# RF.net
KiCad netlist of a schematic drawn in Altium Designer
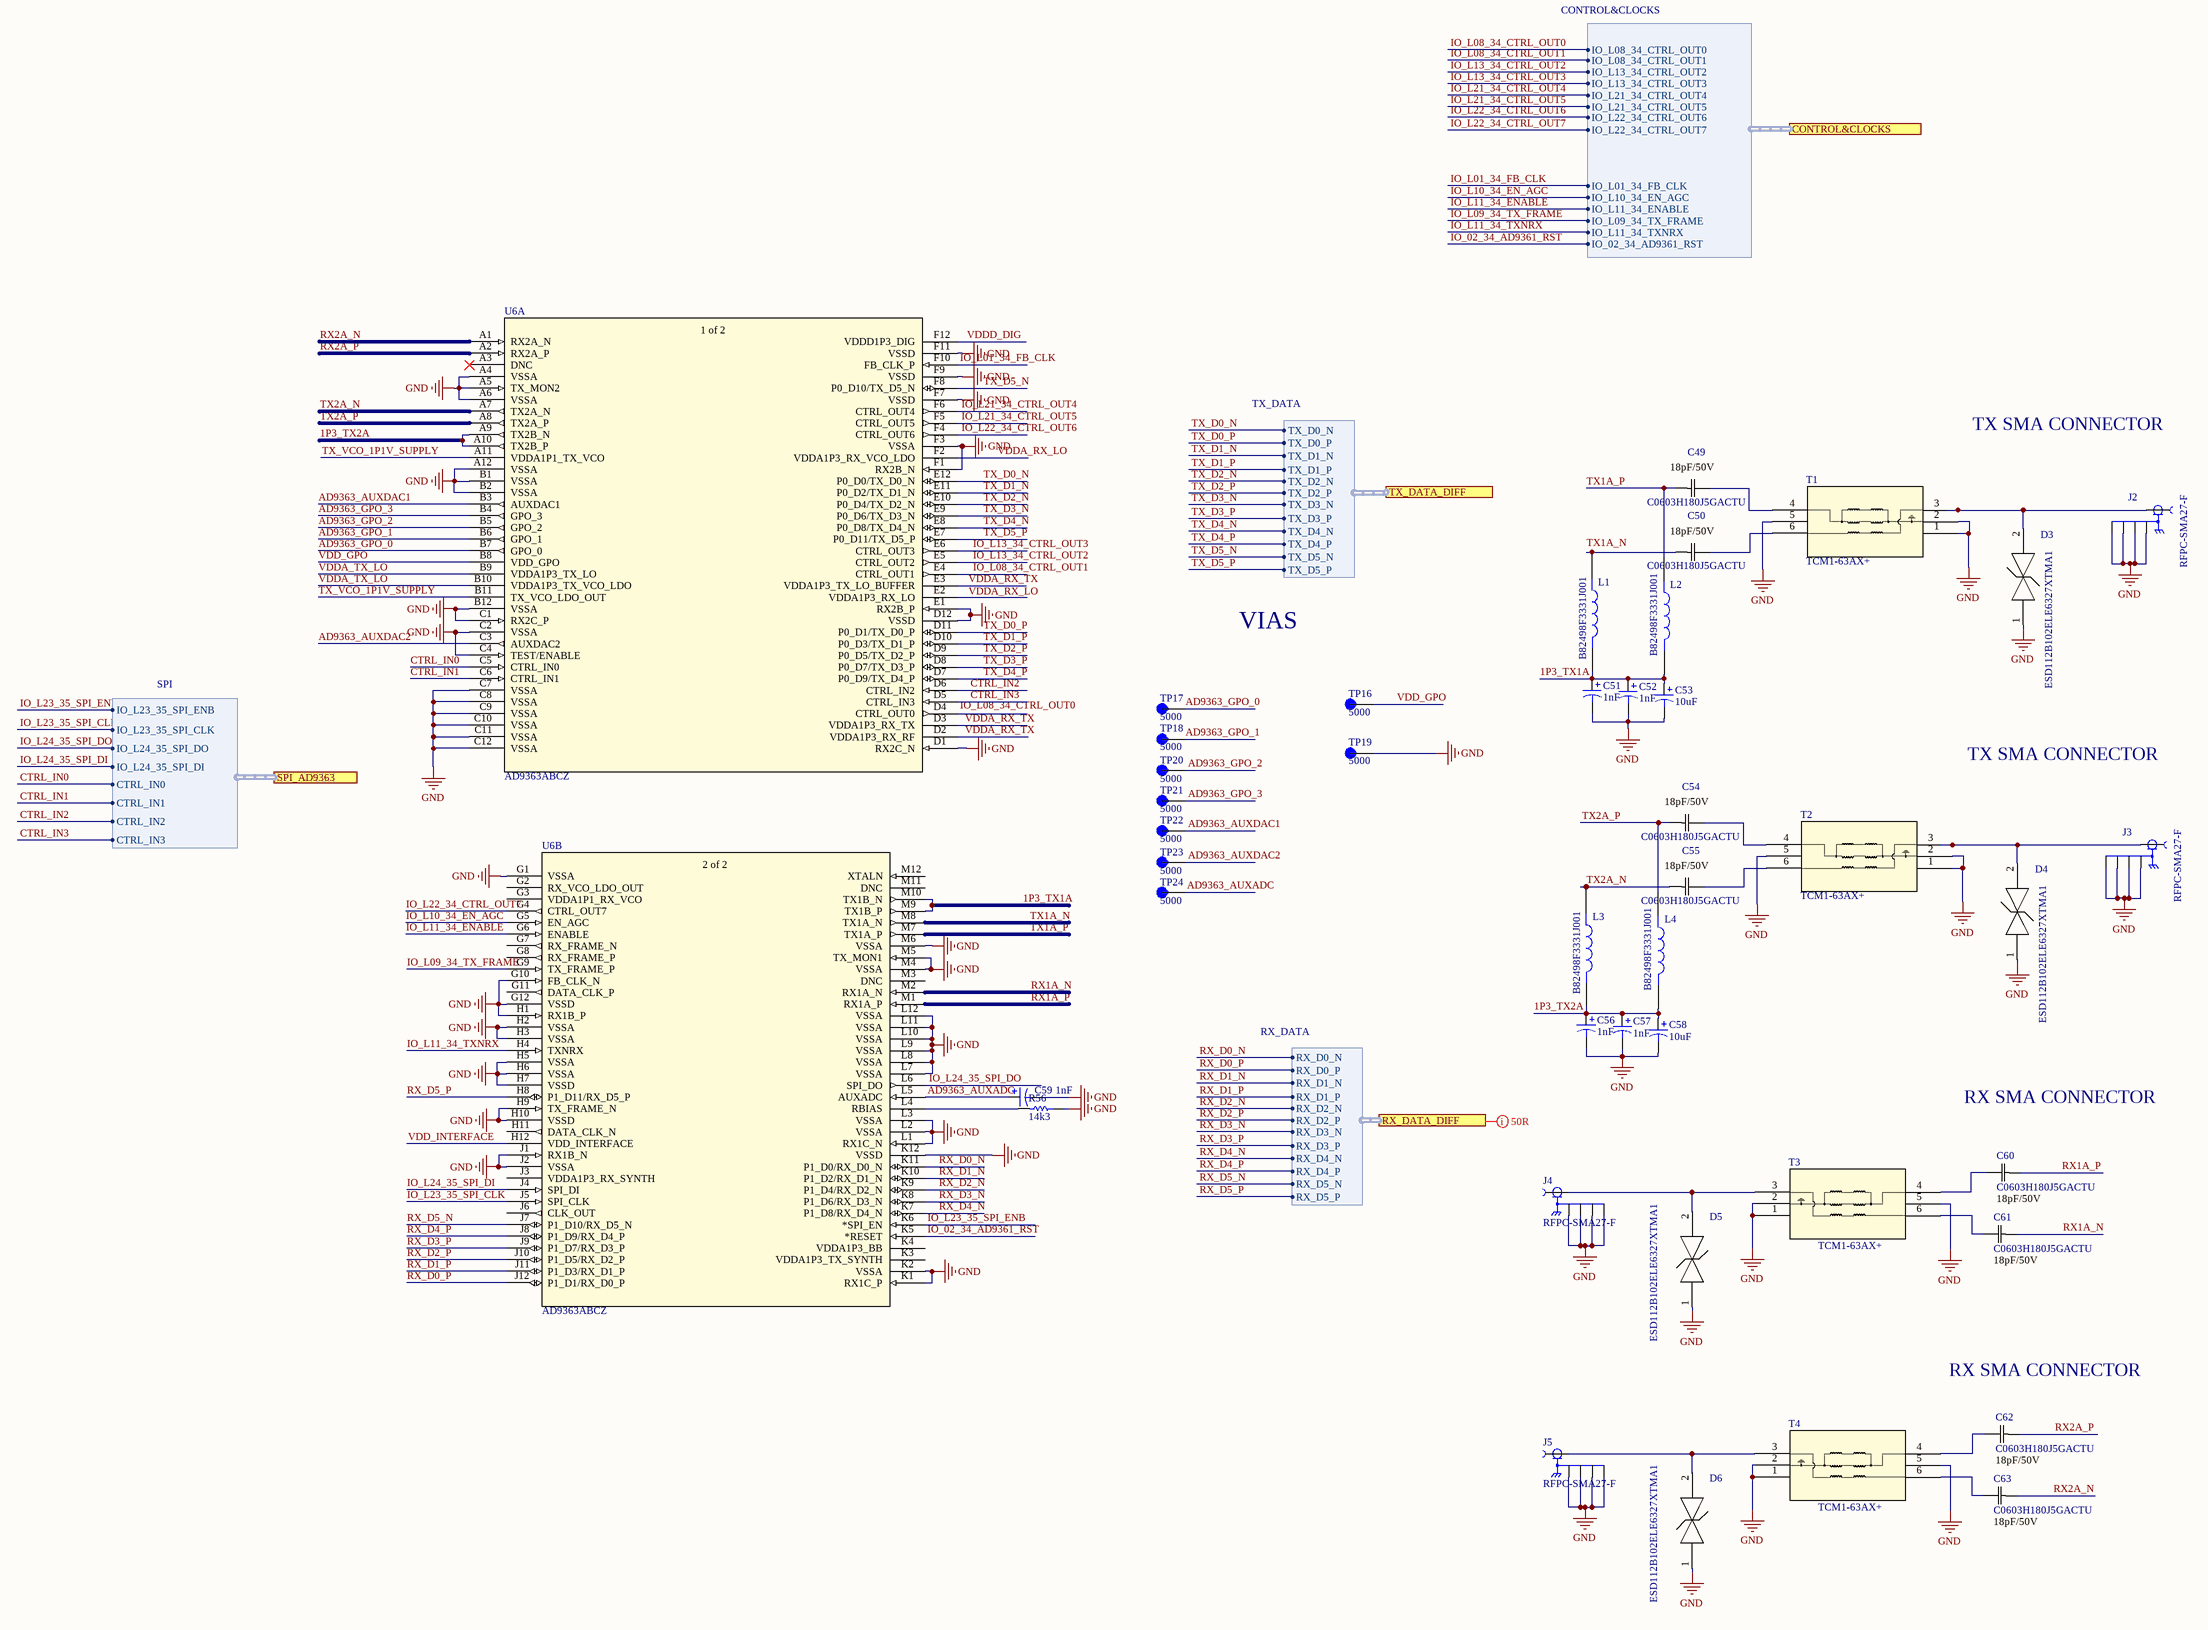
[diagram p0: RF.SchDoc]

(export (version "E")
  (design (tool "Eeschema 10.0.6"))
  (components
    (comp (ref "C49")
      (value "C0603H180J5GACTU")
      (footprint "CAPC17595_87N_KEM")
      (description "No Description Available")
      (fields (field (name "REFDES") "18pF/50V"))
      (libsource (lib "C0603H180J5GACTU") (part "C0603H180J5GACTU"))
    )
    (comp (ref "C50")
      (value "C0603H180J5GACTU")
      (footprint "CAPC17595_87N_KEM")
      (description "No Description Available")
      (fields (field (name "REFDES") "18pF/50V"))
      (libsource (lib "C0603H180J5GACTU") (part "C0603H180J5GACTU"))
    )
    (comp (ref "C51")
      (value "1nF")
      (footprint "C0805")
      (description "Polarized Capacitor (Surface Mount)")
      (fields (field (name "Comment") "Cap Pol3") (field (name "PUBLISHER") "Altium Limited"))
      (libsource (lib "Miscellaneous Devices") (part "Cap Pol3"))
    )
    (comp (ref "C52")
      (value "1nF")
      (footprint "C0805")
      (description "Polarized Capacitor (Surface Mount)")
      (fields (field (name "Comment") "Cap Pol3") (field (name "PUBLISHER") "Altium Limited"))
      (libsource (lib "Miscellaneous Devices") (part "Cap Pol3"))
    )
    (comp (ref "C53")
      (value "10uF")
      (footprint "C0805")
      (description "Polarized Capacitor (Surface Mount)")
      (fields (field (name "Comment") "Cap Pol3") (field (name "PUBLISHER") "Altium Limited"))
      (libsource (lib "Miscellaneous Devices") (part "Cap Pol3"))
    )
    (comp (ref "C54")
      (value "C0603H180J5GACTU")
      (footprint "CAPC17595_87N_KEM")
      (description "No Description Available")
      (fields (field (name "REFDES") "18pF/50V"))
      (libsource (lib "C0603H180J5GACTU") (part "C0603H180J5GACTU"))
    )
    (comp (ref "C55")
      (value "C0603H180J5GACTU")
      (footprint "CAPC17595_87N_KEM")
      (description "No Description Available")
      (fields (field (name "REFDES") "18pF/50V"))
      (libsource (lib "C0603H180J5GACTU") (part "C0603H180J5GACTU"))
    )
    (comp (ref "C56")
      (value "1nF")
      (footprint "C0805")
      (description "Polarized Capacitor (Surface Mount)")
      (fields (field (name "Comment") "Cap Pol3") (field (name "PUBLISHER") "Altium Limited"))
      (libsource (lib "Miscellaneous Devices") (part "Cap Pol3"))
    )
    (comp (ref "C57")
      (value "1nF")
      (footprint "C0805")
      (description "Polarized Capacitor (Surface Mount)")
      (fields (field (name "Comment") "Cap Pol3") (field (name "PUBLISHER") "Altium Limited"))
      (libsource (lib "Miscellaneous Devices") (part "Cap Pol3"))
    )
    (comp (ref "C58")
      (value "10uF")
      (footprint "C0805")
      (description "Polarized Capacitor (Surface Mount)")
      (fields (field (name "Comment") "Cap Pol3") (field (name "PUBLISHER") "Altium Limited"))
      (libsource (lib "Miscellaneous Devices") (part "Cap Pol3"))
    )
    (comp (ref "C59")
      (value "1nF")
      (footprint "C0805")
      (description "Polarized Capacitor (Surface Mount)")
      (fields (field (name "Comment") "Cap Pol3") (field (name "PUBLISHER") "Altium Limited"))
      (libsource (lib "Miscellaneous Devices") (part "Cap Pol3"))
    )
    (comp (ref "C60")
      (value "C0603H180J5GACTU")
      (footprint "CAPC17595_87N_KEM")
      (description "No Description Available")
      (fields (field (name "REFDES") "18pF/50V"))
      (libsource (lib "C0603H180J5GACTU") (part "C0603H180J5GACTU"))
    )
    (comp (ref "C61")
      (value "C0603H180J5GACTU")
      (footprint "CAPC17595_87N_KEM")
      (description "No Description Available")
      (fields (field (name "REFDES") "18pF/50V"))
      (libsource (lib "C0603H180J5GACTU") (part "C0603H180J5GACTU"))
    )
    (comp (ref "C62")
      (value "C0603H180J5GACTU")
      (footprint "CAPC17595_87N_KEM")
      (description "No Description Available")
      (fields (field (name "REFDES") "18pF/50V"))
      (libsource (lib "C0603H180J5GACTU") (part "C0603H180J5GACTU"))
    )
    (comp (ref "C63")
      (value "C0603H180J5GACTU")
      (footprint "CAPC17595_87N_KEM")
      (description "No Description Available")
      (fields (field (name "REFDES") "18pF/50V"))
      (libsource (lib "C0603H180J5GACTU") (part "C0603H180J5GACTU"))
    )
    (comp (ref "D3")
      (value "ESD112B102ELE6327XTMA1")
      (footprint "DIODFN100X60X43-2N")
      (description "TVS RF PLUTO")
      (libsource (lib "TVSESD112B102ELE6327XTMA1") (part "ESD112B102ELE6327XTMA1"))
    )
    (comp (ref "D4")
      (value "ESD112B102ELE6327XTMA1")
      (footprint "DIODFN100X60X43-2N")
      (description "TVS RF PLUTO")
      (libsource (lib "TVSESD112B102ELE6327XTMA1") (part "ESD112B102ELE6327XTMA1"))
    )
    (comp (ref "D5")
      (value "ESD112B102ELE6327XTMA1")
      (footprint "DIODFN100X60X43-2N")
      (description "TVS RF PLUTO")
      (libsource (lib "TVSESD112B102ELE6327XTMA1") (part "ESD112B102ELE6327XTMA1"))
    )
    (comp (ref "D6")
      (value "ESD112B102ELE6327XTMA1")
      (footprint "DIODFN100X60X43-2N")
      (description "TVS RF PLUTO")
      (libsource (lib "TVSESD112B102ELE6327XTMA1") (part "ESD112B102ELE6327XTMA1"))
    )
    (comp (ref "J2")
      (value "RFPC-SMA27-F")
      (footprint "GRADCONN_RFPC-SMA27-F")
      (fields (field (name "MF") "{'manufacturer': u'GCT (Gradconn)'}"))
      (libsource (lib "RFPC-SMA27-F") (part "RFPC-SMA27-F"))
    )
    (comp (ref "J3")
      (value "RFPC-SMA27-F")
      (footprint "GRADCONN_RFPC-SMA27-F")
      (fields (field (name "MF") "{'manufacturer': u'GCT (Gradconn)'}"))
      (libsource (lib "RFPC-SMA27-F") (part "RFPC-SMA27-F"))
    )
    (comp (ref "J4")
      (value "RFPC-SMA27-F")
      (footprint "GRADCONN_RFPC-SMA27-F")
      (fields (field (name "MF") "{'manufacturer': u'GCT (Gradconn)'}"))
      (libsource (lib "") (part "RFPC-SMA27-F_1"))
    )
    (comp (ref "J5")
      (value "RFPC-SMA27-F")
      (footprint "GRADCONN_RFPC-SMA27-F")
      (fields (field (name "MF") "{'manufacturer': u'GCT (Gradconn)'}"))
      (libsource (lib "") (part "RFPC-SMA27-F_1"))
    )
    (comp (ref "L1")
      (value "B82498F3331J001")
      (footprint "IND_B82498F3331J001")
      (fields (field (name "MF") "TDK"))
      (libsource (lib "ID_330nH_B82498F3331J001") (part "B82498F3331J001"))
    )
    (comp (ref "L2")
      (value "B82498F3331J001")
      (footprint "IND_B82498F3331J001")
      (fields (field (name "MF") "TDK"))
      (libsource (lib "ID_330nH_B82498F3331J001") (part "B82498F3331J001"))
    )
    (comp (ref "L3")
      (value "B82498F3331J001")
      (footprint "IND_B82498F3331J001")
      (fields (field (name "MF") "TDK"))
      (libsource (lib "ID_330nH_B82498F3331J001") (part "B82498F3331J001"))
    )
    (comp (ref "L4")
      (value "B82498F3331J001")
      (footprint "IND_B82498F3331J001")
      (fields (field (name "MF") "TDK"))
      (libsource (lib "ID_330nH_B82498F3331J001") (part "B82498F3331J001"))
    )
    (comp (ref "R56")
      (value "14k3")
      (footprint "0603")
      (description "Resistor")
      (fields
        (field (name "MANUFACTURER") "Generic Components")
        (field (name "Comment") "Res1")
        (field (name "PUBLISHER") "Altium Limited")
      )
      (libsource (lib "lib_protel_HC") (part "Res1_1"))
    )
    (comp (ref "T1")
      (value "TCM1-63AX+")
      (footprint "DB1627_MNC")
      (description "No Description Available")
      (libsource (lib "TCM1-63AX&plus_") (part "TCM1-63AX+"))
    )
    (comp (ref "T2")
      (value "TCM1-63AX+")
      (footprint "DB1627_MNC")
      (description "No Description Available")
      (libsource (lib "TCM1-63AX&plus_") (part "TCM1-63AX+"))
    )
    (comp (ref "T3")
      (value "TCM1-63AX+")
      (footprint "DB1627_MNC")
      (description "No Description Available")
      (libsource (lib "TCM1-63AX&plus_") (part "TCM1-63AX+"))
    )
    (comp (ref "T4")
      (value "TCM1-63AX+")
      (footprint "DB1627_MNC")
      (description "No Description Available")
      (libsource (lib "TCM1-63AX&plus_") (part "TCM1-63AX+"))
    )
    (comp (ref "TP16")
      (value "5000")
      (footprint "KEYSTONE_5000")
      (fields (field (name "MF") "Keystone Electronics"))
      (libsource (lib "5000") (part "5000"))
    )
    (comp (ref "TP17")
      (value "5000")
      (footprint "KEYSTONE_5000")
      (fields (field (name "MF") "Keystone Electronics"))
      (libsource (lib "5000") (part "5000"))
    )
    (comp (ref "TP18")
      (value "5000")
      (footprint "KEYSTONE_5000")
      (fields (field (name "MF") "Keystone Electronics"))
      (libsource (lib "5000") (part "5000"))
    )
    (comp (ref "TP19")
      (value "5000")
      (footprint "KEYSTONE_5000")
      (fields (field (name "MF") "Keystone Electronics"))
      (libsource (lib "5000") (part "5000"))
    )
    (comp (ref "TP20")
      (value "5000")
      (footprint "KEYSTONE_5000")
      (fields (field (name "MF") "Keystone Electronics"))
      (libsource (lib "5000") (part "5000"))
    )
    (comp (ref "TP21")
      (value "5000")
      (footprint "KEYSTONE_5000")
      (fields (field (name "MF") "Keystone Electronics"))
      (libsource (lib "5000") (part "5000"))
    )
    (comp (ref "TP22")
      (value "5000")
      (footprint "KEYSTONE_5000")
      (fields (field (name "MF") "Keystone Electronics"))
      (libsource (lib "5000") (part "5000"))
    )
    (comp (ref "TP23")
      (value "5000")
      (footprint "KEYSTONE_5000")
      (fields (field (name "MF") "Keystone Electronics"))
      (libsource (lib "5000") (part "5000"))
    )
    (comp (ref "TP24")
      (value "5000")
      (footprint "KEYSTONE_5000")
      (fields (field (name "MF") "Keystone Electronics"))
      (libsource (lib "5000") (part "5000"))
    )
    (comp (ref "U6")
      (value "AD9363ABCZ")
      (footprint "BC-144-7_ADI")
      (description "No Description Available")
      (libsource (lib "AD9363ABCZ") (part "AD9363ABCZ"))
    )
  )
  (nets
    (net (code "5") (name "/1P3_TX1A") (class "Default")
      (node (ref "C51") (pin "1") (pinfunction "1_1") (pintype "passive"))
      (node (ref "C52") (pin "1") (pinfunction "1_1") (pintype "passive"))
      (node (ref "C53") (pin "1") (pinfunction "1_1") (pintype "passive"))
      (node (ref "L1") (pin "1") (pinfunction "1_1") (pintype "passive"))
      (node (ref "L2") (pin "1") (pinfunction "1_1") (pintype "passive"))
      (node (ref "U6") (pin "M10") (pinfunction "TX1B_N_M10") (pintype "output"))
      (node (ref "U6") (pin "M9") (pinfunction "TX1B_P_M9") (pintype "output"))
    )
    (net (code "6") (name "/1P3_TX2A") (class "Default")
      (node (ref "C56") (pin "1") (pinfunction "1_1") (pintype "passive"))
      (node (ref "C57") (pin "1") (pinfunction "1_1") (pintype "passive"))
      (node (ref "C58") (pin "1") (pinfunction "1_1") (pintype "passive"))
      (node (ref "L3") (pin "1") (pinfunction "1_1") (pintype "passive"))
      (node (ref "L4") (pin "1") (pinfunction "1_1") (pintype "passive"))
      (node (ref "U6") (pin "A10") (pinfunction "TX2B_P_A10") (pintype "output"))
      (node (ref "U6") (pin "A9") (pinfunction "TX2B_N_A9") (pintype "output"))
    )
    (net (code "7") (name "/AD9363_AUXADC") (class "Default")
      (node (ref "C59") (pin "1") (pinfunction "1_1") (pintype "passive"))
      (node (ref "TP24") (pin "TP") (pinfunction "TP_TP") (pintype "passive"))
      (node (ref "U6") (pin "L5") (pinfunction "AUXADC_L5") (pintype "input"))
    )
    (net (code "8") (name "/AD9363_AUXDAC1") (class "Default")
      (node (ref "TP22") (pin "TP") (pinfunction "TP_TP") (pintype "passive"))
      (node (ref "U6") (pin "B3") (pinfunction "AUXDAC1_B3") (pintype "output"))
    )
    (net (code "9") (name "/AD9363_AUXDAC2") (class "Default")
      (node (ref "TP23") (pin "TP") (pinfunction "TP_TP") (pintype "passive"))
      (node (ref "U6") (pin "C3") (pinfunction "AUXDAC2_C3") (pintype "output"))
    )
    (net (code "10") (name "/AD9363_GPO_0") (class "Default")
      (node (ref "TP17") (pin "TP") (pinfunction "TP_TP") (pintype "passive"))
      (node (ref "U6") (pin "B7") (pinfunction "GPO_0_B7") (pintype "output"))
    )
    (net (code "11") (name "/AD9363_GPO_1") (class "Default")
      (node (ref "TP18") (pin "TP") (pinfunction "TP_TP") (pintype "passive"))
      (node (ref "U6") (pin "B6") (pinfunction "GPO_1_B6") (pintype "output"))
    )
    (net (code "12") (name "/AD9363_GPO_2") (class "Default")
      (node (ref "TP20") (pin "TP") (pinfunction "TP_TP") (pintype "passive"))
      (node (ref "U6") (pin "B5") (pinfunction "GPO_2_B5") (pintype "output"))
    )
    (net (code "13") (name "/AD9363_GPO_3") (class "Default")
      (node (ref "TP21") (pin "TP") (pinfunction "TP_TP") (pintype "passive"))
      (node (ref "U6") (pin "B4") (pinfunction "GPO_3_B4") (pintype "output"))
    )
    (net (code "14") (name "/CTRL_IN0") (class "Default")
      (node (ref "U6") (pin "C5") (pinfunction "CTRL_IN0_C5") (pintype "input"))
    )
    (net (code "15") (name "/CTRL_IN1") (class "Default")
      (node (ref "U6") (pin "C6") (pinfunction "CTRL_IN1_C6") (pintype "input"))
    )
    (net (code "16") (name "/CTRL_IN2") (class "Default")
      (node (ref "U6") (pin "D6") (pinfunction "CTRL_IN2_D6") (pintype "input"))
    )
    (net (code "17") (name "/CTRL_IN3") (class "Default")
      (node (ref "U6") (pin "D5") (pinfunction "CTRL_IN3_D5") (pintype "input"))
    )
    (net (code "18") (name "/IO_02_34_AD9361_RST") (class "Default")
      (node (ref "U6") (pin "K5") (pinfunction "*RESET_K5") (pintype "input"))
    )
    (net (code "19") (name "/IO_L01_34_FB_CLK") (class "Default")
      (node (ref "U6") (pin "F10") (pinfunction "FB_CLK_P_F10") (pintype "input"))
    )
    (net (code "21") (name "/IO_L08_34_CTRL_OUT1") (class "Default")
      (node (ref "U6") (pin "E4") (pinfunction "CTRL_OUT1_E4") (pintype "output"))
    )
    (net (code "22") (name "/IO_L09_34_TX_FRAME") (class "Default")
      (node (ref "U6") (pin "G9") (pinfunction "TX_FRAME_P_G9") (pintype "input"))
    )
    (net (code "23") (name "/IO_L10_34_EN_AGC") (class "Default")
      (node (ref "U6") (pin "G5") (pinfunction "EN_AGC_G5") (pintype "input"))
    )
    (net (code "24") (name "/IO_L11_34_ENABLE") (class "Default")
      (node (ref "U6") (pin "G6") (pinfunction "ENABLE_G6") (pintype "input"))
    )
    (net (code "25") (name "/IO_L11_34_TXNRX") (class "Default")
      (node (ref "U6") (pin "H4") (pinfunction "TXNRX_H4") (pintype "input"))
    )
    (net (code "26") (name "/IO_L13_34_CTRL_OUT2") (class "Default")
      (node (ref "U6") (pin "E5") (pinfunction "CTRL_OUT2_E5") (pintype "output"))
    )
    (net (code "27") (name "/IO_L13_34_CTRL_OUT3") (class "Default")
      (node (ref "U6") (pin "E6") (pinfunction "CTRL_OUT3_E6") (pintype "output"))
    )
    (net (code "28") (name "/IO_L21_34_CTRL_OUT4") (class "Default")
      (node (ref "U6") (pin "F6") (pinfunction "CTRL_OUT4_F6") (pintype "output"))
    )
    (net (code "29") (name "/IO_L21_34_CTRL_OUT5") (class "Default")
      (node (ref "U6") (pin "F5") (pinfunction "CTRL_OUT5_F5") (pintype "output"))
    )
    (net (code "30") (name "/IO_L22_34_CTRL_OUT6") (class "Default")
      (node (ref "U6") (pin "F4") (pinfunction "CTRL_OUT6_F4") (pintype "output"))
    )
    (net (code "31") (name "/IO_L22_34_CTRL_OUT7") (class "Default")
      (node (ref "U6") (pin "G4") (pinfunction "CTRL_OUT7_G4") (pintype "output"))
    )
    (net (code "32") (name "/IO_L23_35_SPI_CLK") (class "Default")
      (node (ref "U6") (pin "J5") (pinfunction "SPI_CLK_J5") (pintype "input"))
    )
    (net (code "33") (name "/IO_L23_35_SPI_ENB") (class "Default")
      (node (ref "U6") (pin "K6") (pinfunction "*SPI_EN_K6") (pintype "input"))
    )
    (net (code "34") (name "/IO_L24_35_SPI_DI") (class "Default")
      (node (ref "U6") (pin "J4") (pinfunction "SPI_DI_J4") (pintype "input"))
    )
    (net (code "35") (name "/IO_L24_35_SPI_DO") (class "Default")
      (node (ref "U6") (pin "L6") (pinfunction "SPI_DO_L6") (pintype "output"))
    )
    (net (code "36") (name "/RX1A_N") (class "Default")
      (node (ref "C61") (pin "1") (pinfunction "1_1") (pintype "passive"))
      (node (ref "U6") (pin "M2") (pinfunction "RX1A_N_M2") (pintype "input"))
    )
    (net (code "37") (name "/RX1A_P") (class "Default")
      (node (ref "C60") (pin "1") (pinfunction "1_1") (pintype "passive"))
      (node (ref "U6") (pin "M1") (pinfunction "RX1A_P_M1") (pintype "input"))
    )
    (net (code "38") (name "/RX2A_N") (class "Default")
      (node (ref "C63") (pin "1") (pinfunction "1_1") (pintype "passive"))
      (node (ref "U6") (pin "A1") (pinfunction "RX2A_N_A1") (pintype "input"))
    )
    (net (code "39") (name "/RX2A_P") (class "Default")
      (node (ref "C62") (pin "1") (pinfunction "1_1") (pintype "passive"))
      (node (ref "U6") (pin "A2") (pinfunction "RX2A_P_A2") (pintype "input"))
    )
    (net (code "40") (name "/RX_D0_N") (class "Default")
      (node (ref "U6") (pin "K11") (pinfunction "P1_D0/RX_D0_N_K11") (pintype "bidirectional"))
    )
    (net (code "41") (name "/RX_D0_P") (class "Default")
      (node (ref "U6") (pin "J12") (pinfunction "P1_D1/RX_D0_P_J12") (pintype "bidirectional"))
    )
    (net (code "42") (name "/RX_D1_N") (class "Default")
      (node (ref "U6") (pin "K10") (pinfunction "P1_D2/RX_D1_N_K10") (pintype "bidirectional"))
    )
    (net (code "43") (name "/RX_D1_P") (class "Default")
      (node (ref "U6") (pin "J11") (pinfunction "P1_D3/RX_D1_P_J11") (pintype "bidirectional"))
    )
    (net (code "44") (name "/RX_D2_N") (class "Default")
      (node (ref "U6") (pin "K9") (pinfunction "P1_D4/RX_D2_N_K9") (pintype "bidirectional"))
    )
    (net (code "45") (name "/RX_D2_P") (class "Default")
      (node (ref "U6") (pin "J10") (pinfunction "P1_D5/RX_D2_P_J10") (pintype "bidirectional"))
    )
    (net (code "46") (name "/RX_D3_N") (class "Default")
      (node (ref "U6") (pin "K8") (pinfunction "P1_D6/RX_D3_N_K8") (pintype "bidirectional"))
    )
    (net (code "47") (name "/RX_D3_P") (class "Default")
      (node (ref "U6") (pin "J9") (pinfunction "P1_D7/RX_D3_P_J9") (pintype "bidirectional"))
    )
    (net (code "48") (name "/RX_D4_N") (class "Default")
      (node (ref "U6") (pin "K7") (pinfunction "P1_D8/RX_D4_N_K7") (pintype "bidirectional"))
    )
    (net (code "49") (name "/RX_D4_P") (class "Default")
      (node (ref "U6") (pin "J8") (pinfunction "P1_D9/RX_D4_P_J8") (pintype "bidirectional"))
    )
    (net (code "50") (name "/RX_D5_N") (class "Default")
      (node (ref "U6") (pin "J7") (pinfunction "P1_D10/RX_D5_N_J7") (pintype "bidirectional"))
    )
    (net (code "51") (name "/RX_D5_P") (class "Default")
      (node (ref "U6") (pin "H8") (pinfunction "P1_D11/RX_D5_P_H8") (pintype "bidirectional"))
    )
    (net (code "52") (name "/TX1A_N") (class "Default")
      (node (ref "U6") (pin "M8") (pinfunction "TX1A_N_M8") (pintype "output"))
    )
    (net (code "53") (name "/TX1A_P") (class "Default")
      (node (ref "C49") (pin "1") (pinfunction "1_1") (pintype "passive"))
      (node (ref "L2") (pin "2") (pinfunction "2_2") (pintype "passive"))
      (node (ref "U6") (pin "M7") (pinfunction "TX1A_P_M7") (pintype "output"))
    )
    (net (code "54") (name "/TX2A_N") (class "Default")
      (node (ref "C55") (pin "1") (pinfunction "1_1") (pintype "passive"))
      (node (ref "L3") (pin "2") (pinfunction "2_2") (pintype "passive"))
      (node (ref "U6") (pin "A7") (pinfunction "TX2A_N_A7") (pintype "output"))
    )
    (net (code "55") (name "/TX2A_P") (class "Default")
      (node (ref "C54") (pin "1") (pinfunction "1_1") (pintype "passive"))
      (node (ref "L4") (pin "2") (pinfunction "2_2") (pintype "passive"))
      (node (ref "U6") (pin "A8") (pinfunction "TX2A_P_A8") (pintype "output"))
    )
    (net (code "56") (name "/TX_D0_N") (class "Default")
      (node (ref "U6") (pin "E12") (pinfunction "P0_D0/TX_D0_N_E12") (pintype "bidirectional"))
    )
    (net (code "57") (name "/TX_D0_P") (class "Default")
      (node (ref "U6") (pin "D11") (pinfunction "P0_D1/TX_D0_P_D11") (pintype "bidirectional"))
    )
    (net (code "58") (name "/TX_D1_N") (class "Default")
      (node (ref "U6") (pin "E11") (pinfunction "P0_D2/TX_D1_N_E11") (pintype "bidirectional"))
    )
    (net (code "59") (name "/TX_D1_P") (class "Default")
      (node (ref "U6") (pin "D10") (pinfunction "P0_D3/TX_D1_P_D10") (pintype "bidirectional"))
    )
    (net (code "60") (name "/TX_D2_N") (class "Default")
      (node (ref "U6") (pin "E10") (pinfunction "P0_D4/TX_D2_N_E10") (pintype "bidirectional"))
    )
    (net (code "61") (name "/TX_D2_P") (class "Default")
      (node (ref "U6") (pin "D9") (pinfunction "P0_D5/TX_D2_P_D9") (pintype "bidirectional"))
    )
    (net (code "62") (name "/TX_D3_N") (class "Default")
      (node (ref "U6") (pin "E9") (pinfunction "P0_D6/TX_D3_N_E9") (pintype "bidirectional"))
    )
    (net (code "63") (name "/TX_D3_P") (class "Default")
      (node (ref "U6") (pin "D8") (pinfunction "P0_D7/TX_D3_P_D8") (pintype "bidirectional"))
    )
    (net (code "64") (name "/TX_D4_N") (class "Default")
      (node (ref "U6") (pin "E8") (pinfunction "P0_D8/TX_D4_N_E8") (pintype "bidirectional"))
    )
    (net (code "65") (name "/TX_D4_P") (class "Default")
      (node (ref "U6") (pin "D7") (pinfunction "P0_D9/TX_D4_P_D7") (pintype "bidirectional"))
    )
    (net (code "66") (name "/TX_D5_N") (class "Default")
      (node (ref "U6") (pin "F8") (pinfunction "P0_D10/TX_D5_N_F8") (pintype "bidirectional"))
    )
    (net (code "67") (name "/TX_D5_P") (class "Default")
      (node (ref "U6") (pin "E7") (pinfunction "P0_D11/TX_D5_P_E7") (pintype "bidirectional"))
    )
    (net (code "68") (name "/TX_VCO_1P1V_SUPPLY") (class "Default")
      (node (ref "U6") (pin "A11") (pinfunction "VDDA1P1_TX_VCO_A11") (pintype "power_in"))
      (node (ref "U6") (pin "B11") (pinfunction "TX_VCO_LDO_OUT_B11") (pintype "power_in"))
    )
    (net (code "69") (name "/VDDA_RX_LO") (class "Default")
      (node (ref "U6") (pin "F2") (pinfunction "VDDA1P3_RX_VCO_LDO_F2") (pintype "power_in"))
    )
    (net (code "70") (name "/VDDA_RX_TX") (class "Default")
      (node (ref "U6") (pin "D2") (pinfunction "VDDA1P3_RX_RF_D2") (pintype "power_in"))
      (node (ref "U6") (pin "D3") (pinfunction "VDDA1P3_RX_TX_D3") (pintype "power_in"))
      (node (ref "U6") (pin "E3") (pinfunction "VDDA1P3_TX_LO_BUFFER_E3") (pintype "power_in"))
    )
    (net (code "71") (name "/VDDA_TX_LO") (class "Default")
      (node (ref "U6") (pin "B10") (pinfunction "VDDA1P3_TX_VCO_LDO_B10") (pintype "power_in"))
      (node (ref "U6") (pin "B9") (pinfunction "VDDA1P3_TX_LO_B9") (pintype "power_in"))
    )
    (net (code "72") (name "/VDDD_DIG") (class "Default")
      (node (ref "U6") (pin "F12") (pinfunction "VDDD1P3_DIG_F12") (pintype "power_in"))
    )
    (net (code "73") (name "/VDD_GPO") (class "Default")
      (node (ref "TP16") (pin "TP") (pinfunction "TP_TP") (pintype "passive"))
      (node (ref "U6") (pin "B8") (pinfunction "VDD_GPO_B8") (pintype "power_in"))
    )
    (net (code "74") (name "/VDD_INTERFACE") (class "Default")
      (node (ref "U6") (pin "H12") (pinfunction "VDD_INTERFACE_H12") (pintype "power_in"))
    )
    (net (code "79") (name "GND") (class "Default")
      (node (ref "C51") (pin "2") (pinfunction "2_2") (pintype "passive"))
      (node (ref "C52") (pin "2") (pinfunction "2_2") (pintype "passive"))
      (node (ref "C53") (pin "2") (pinfunction "2_2") (pintype "passive"))
      (node (ref "C56") (pin "2") (pinfunction "2_2") (pintype "passive"))
      (node (ref "C57") (pin "2") (pinfunction "2_2") (pintype "passive"))
      (node (ref "C58") (pin "2") (pinfunction "2_2") (pintype "passive"))
      (node (ref "C59") (pin "2") (pinfunction "2_2") (pintype "passive"))
      (node (ref "J2") (pin "G1") (pinfunction "G1_G1") (pintype "power_in"))
      (node (ref "J2") (pin "G2") (pinfunction "G2_G2") (pintype "power_in"))
      (node (ref "J2") (pin "G3") (pinfunction "G3_G3") (pintype "power_in"))
      (node (ref "J2") (pin "G4") (pinfunction "G4_G4") (pintype "power_in"))
      (node (ref "J3") (pin "G1") (pinfunction "G1_G1") (pintype "power_in"))
      (node (ref "J3") (pin "G2") (pinfunction "G2_G2") (pintype "power_in"))
      (node (ref "J3") (pin "G3") (pinfunction "G3_G3") (pintype "power_in"))
      (node (ref "J3") (pin "G4") (pinfunction "G4_G4") (pintype "power_in"))
      (node (ref "J4") (pin "G1") (pinfunction "G1_G1") (pintype "power_in"))
      (node (ref "J4") (pin "G2") (pinfunction "G2_G2") (pintype "power_in"))
      (node (ref "J4") (pin "G3") (pinfunction "G3_G3") (pintype "power_in"))
      (node (ref "J4") (pin "G4") (pinfunction "G4_G4") (pintype "power_in"))
      (node (ref "J5") (pin "G1") (pinfunction "G1_G1") (pintype "power_in"))
      (node (ref "J5") (pin "G2") (pinfunction "G2_G2") (pintype "power_in"))
      (node (ref "J5") (pin "G3") (pinfunction "G3_G3") (pintype "power_in"))
      (node (ref "J5") (pin "G4") (pinfunction "G4_G4") (pintype "power_in"))
      (node (ref "R56") (pin "1") (pinfunction "1_1") (pintype "passive"))
      (node (ref "T1") (pin "1") (pinfunction "1_1") (pintype "passive"))
      (node (ref "T1") (pin "2") (pinfunction "2_2") (pintype "passive"))
      (node (ref "T1") (pin "5") (pinfunction "5_5") (pintype "passive"))
      (node (ref "T2") (pin "1") (pinfunction "1_1") (pintype "passive"))
      (node (ref "T2") (pin "2") (pinfunction "2_2") (pintype "passive"))
      (node (ref "T2") (pin "5") (pinfunction "5_5") (pintype "passive"))
      (node (ref "T3") (pin "1") (pinfunction "1_1") (pintype "passive"))
      (node (ref "T3") (pin "2") (pinfunction "2_2") (pintype "passive"))
      (node (ref "T3") (pin "5") (pinfunction "5_5") (pintype "passive"))
      (node (ref "T4") (pin "1") (pinfunction "1_1") (pintype "passive"))
      (node (ref "T4") (pin "2") (pinfunction "2_2") (pintype "passive"))
      (node (ref "T4") (pin "5") (pinfunction "5_5") (pintype "passive"))
      (node (ref "TP19") (pin "TP") (pinfunction "TP_TP") (pintype "passive"))
      (node (ref "U6") (pin "A12") (pinfunction "VSSA_A12") (pintype "power_in"))
      (node (ref "U6") (pin "A4") (pinfunction "VSSA_A4") (pintype "power_in"))
      (node (ref "U6") (pin "A5") (pinfunction "TX_MON2_A5") (pintype "input"))
      (node (ref "U6") (pin "A6") (pinfunction "VSSA_A6") (pintype "power_in"))
      (node (ref "U6") (pin "B1") (pinfunction "VSSA_B1") (pintype "power_in"))
      (node (ref "U6") (pin "B12") (pinfunction "VSSA_B12") (pintype "power_in"))
      (node (ref "U6") (pin "B2") (pinfunction "VSSA_B2") (pintype "power_in"))
      (node (ref "U6") (pin "C1") (pinfunction "RX2C_P_C1") (pintype "input"))
      (node (ref "U6") (pin "C10") (pinfunction "VSSA_C10") (pintype "power_in"))
      (node (ref "U6") (pin "C11") (pinfunction "VSSA_C11") (pintype "power_in"))
      (node (ref "U6") (pin "C12") (pinfunction "VSSA_C12") (pintype "power_in"))
      (node (ref "U6") (pin "C2") (pinfunction "VSSA_C2") (pintype "power_in"))
      (node (ref "U6") (pin "C4") (pinfunction "TEST/ENABLE_C4") (pintype "input"))
      (node (ref "U6") (pin "C7") (pinfunction "VSSA_C7") (pintype "power_in"))
      (node (ref "U6") (pin "C8") (pinfunction "VSSA_C8") (pintype "power_in"))
      (node (ref "U6") (pin "C9") (pinfunction "VSSA_C9") (pintype "power_in"))
      (node (ref "U6") (pin "D1") (pinfunction "RX2C_N_D1") (pintype "input"))
      (node (ref "U6") (pin "D12") (pinfunction "VSSD_D12") (pintype "power_in"))
      (node (ref "U6") (pin "E1") (pinfunction "RX2B_P_E1") (pintype "input"))
      (node (ref "U6") (pin "F1") (pinfunction "RX2B_N_F1") (pintype "input"))
      (node (ref "U6") (pin "F11") (pinfunction "VSSD_F11") (pintype "power_in"))
      (node (ref "U6") (pin "F3") (pinfunction "VSSA_F3") (pintype "power_in"))
      (node (ref "U6") (pin "F7") (pinfunction "VSSD_F7") (pintype "power_in"))
      (node (ref "U6") (pin "F9") (pinfunction "VSSD_F9") (pintype "power_in"))
      (node (ref "U6") (pin "G1") (pinfunction "VSSA_G1") (pintype "power_in"))
      (node (ref "U6") (pin "G10") (pinfunction "FB_CLK_N_G10") (pintype "input"))
      (node (ref "U6") (pin "G12") (pinfunction "VSSD_G12") (pintype "power_in"))
      (node (ref "U6") (pin "H1") (pinfunction "RX1B_P_H1") (pintype "input"))
      (node (ref "U6") (pin "H10") (pinfunction "VSSD_H10") (pintype "power_in"))
      (node (ref "U6") (pin "H2") (pinfunction "VSSA_H2") (pintype "power_in"))
      (node (ref "U6") (pin "H3") (pinfunction "VSSA_H3") (pintype "power_in"))
      (node (ref "U6") (pin "H5") (pinfunction "VSSA_H5") (pintype "power_in"))
      (node (ref "U6") (pin "H6") (pinfunction "VSSA_H6") (pintype "power_in"))
      (node (ref "U6") (pin "H7") (pinfunction "VSSD_H7") (pintype "power_in"))
      (node (ref "U6") (pin "H9") (pinfunction "TX_FRAME_N_H9") (pintype "input"))
      (node (ref "U6") (pin "J1") (pinfunction "RX1B_N_J1") (pintype "input"))
      (node (ref "U6") (pin "J2") (pinfunction "VSSA_J2") (pintype "power_in"))
      (node (ref "U6") (pin "K1") (pinfunction "RX1C_P_K1") (pintype "input"))
      (node (ref "U6") (pin "K12") (pinfunction "VSSD_K12") (pintype "power_in"))
      (node (ref "U6") (pin "K2") (pinfunction "VSSA_K2") (pintype "power_in"))
      (node (ref "U6") (pin "L1") (pinfunction "RX1C_N_L1") (pintype "input"))
      (node (ref "U6") (pin "L10") (pinfunction "VSSA_L10") (pintype "power_in"))
      (node (ref "U6") (pin "L11") (pinfunction "VSSA_L11") (pintype "power_in"))
      (node (ref "U6") (pin "L12") (pinfunction "VSSA_L12") (pintype "power_in"))
      (node (ref "U6") (pin "L2") (pinfunction "VSSA_L2") (pintype "power_in"))
      (node (ref "U6") (pin "L3") (pinfunction "VSSA_L3") (pintype "power_in"))
      (node (ref "U6") (pin "L7") (pinfunction "VSSA_L7") (pintype "power_in"))
      (node (ref "U6") (pin "L8") (pinfunction "VSSA_L8") (pintype "power_in"))
      (node (ref "U6") (pin "L9") (pinfunction "VSSA_L9") (pintype "power_in"))
      (node (ref "U6") (pin "M4") (pinfunction "VSSA_M4") (pintype "power_in"))
      (node (ref "U6") (pin "M5") (pinfunction "TX_MON1_M5") (pintype "input"))
      (node (ref "U6") (pin "M6") (pinfunction "VSSA_M6") (pintype "power_in"))
    )
    (net (code "80") (name "Net-(C49-Pad2)") (class "Default")
      (node (ref "C49") (pin "2") (pinfunction "2_2") (pintype "passive"))
      (node (ref "T1") (pin "4") (pinfunction "4_4") (pintype "passive"))
    )
    (net (code "81") (name "Net-(C50-Pad1)") (class "Default")
      (node (ref "C50") (pin "1") (pinfunction "1_1") (pintype "passive"))
      (node (ref "L1") (pin "2") (pinfunction "2_2") (pintype "passive"))
    )
    (net (code "82") (name "Net-(C50-Pad2)") (class "Default")
      (node (ref "C50") (pin "2") (pinfunction "2_2") (pintype "passive"))
      (node (ref "T1") (pin "6") (pinfunction "6_6") (pintype "passive"))
    )
    (net (code "83") (name "Net-(C54-Pad2)") (class "Default")
      (node (ref "C54") (pin "2") (pinfunction "2_2") (pintype "passive"))
      (node (ref "T2") (pin "4") (pinfunction "4_4") (pintype "passive"))
    )
    (net (code "84") (name "Net-(C55-Pad2)") (class "Default")
      (node (ref "C55") (pin "2") (pinfunction "2_2") (pintype "passive"))
      (node (ref "T2") (pin "6") (pinfunction "6_6") (pintype "passive"))
    )
    (net (code "85") (name "Net-(C60-Pad2)") (class "Default")
      (node (ref "C60") (pin "2") (pinfunction "2_2") (pintype "passive"))
      (node (ref "T3") (pin "4") (pinfunction "4_4") (pintype "passive"))
    )
    (net (code "86") (name "Net-(C61-Pad2)") (class "Default")
      (node (ref "C61") (pin "2") (pinfunction "2_2") (pintype "passive"))
      (node (ref "T3") (pin "6") (pinfunction "6_6") (pintype "passive"))
    )
    (net (code "87") (name "Net-(C62-Pad2)") (class "Default")
      (node (ref "C62") (pin "2") (pinfunction "2_2") (pintype "passive"))
      (node (ref "T4") (pin "4") (pinfunction "4_4") (pintype "passive"))
    )
    (net (code "88") (name "Net-(C63-Pad2)") (class "Default")
      (node (ref "C63") (pin "2") (pinfunction "2_2") (pintype "passive"))
      (node (ref "T4") (pin "6") (pinfunction "6_6") (pintype "passive"))
    )
    (net (code "89") (name "Net-(J2-Pad1)") (class "Default")
      (node (ref "J2") (pin "1") (pinfunction "1_1") (pintype "passive"))
      (node (ref "T1") (pin "3") (pinfunction "3_3") (pintype "passive"))
    )
    (net (code "90") (name "Net-(J3-Pad1)") (class "Default")
      (node (ref "J3") (pin "1") (pinfunction "1_1") (pintype "passive"))
      (node (ref "T2") (pin "3") (pinfunction "3_3") (pintype "passive"))
    )
    (net (code "91") (name "Net-(J4-Pad1)") (class "Default")
      (node (ref "J4") (pin "1") (pinfunction "1_1") (pintype "passive"))
      (node (ref "T3") (pin "3") (pinfunction "3_3") (pintype "passive"))
    )
    (net (code "92") (name "Net-(J5-Pad1)") (class "Default")
      (node (ref "J5") (pin "1") (pinfunction "1_1") (pintype "passive"))
      (node (ref "T4") (pin "3") (pinfunction "3_3") (pintype "passive"))
    )
    (net (code "93") (name "Net-(U6B-RBIAS)") (class "Default")
      (node (ref "R56") (pin "2") (pinfunction "2_2") (pintype "passive"))
      (node (ref "U6") (pin "L4") (pinfunction "RBIAS_L4") (pintype "power_in"))
    )
    (net (code "94") (name "unconnected-(D3-Pad1)") (class "Default")
      (node (ref "D3") (pin "1") (pintype "passive"))
    )
    (net (code "95") (name "unconnected-(D3-Pad2)") (class "Default")
      (node (ref "D3") (pin "2") (pintype "passive"))
    )
    (net (code "96") (name "unconnected-(D4-Pad1)") (class "Default")
      (node (ref "D4") (pin "1") (pintype "passive"))
    )
    (net (code "97") (name "unconnected-(D4-Pad2)") (class "Default")
      (node (ref "D4") (pin "2") (pintype "passive"))
    )
    (net (code "98") (name "unconnected-(D5-Pad1)") (class "Default")
      (node (ref "D5") (pin "1") (pintype "passive"))
    )
    (net (code "99") (name "unconnected-(D5-Pad2)") (class "Default")
      (node (ref "D5") (pin "2") (pintype "passive"))
    )
    (net (code "100") (name "unconnected-(D6-Pad1)") (class "Default")
      (node (ref "D6") (pin "1") (pintype "passive"))
    )
    (net (code "101") (name "unconnected-(D6-Pad2)") (class "Default")
      (node (ref "D6") (pin "2") (pintype "passive"))
    )
    (net (code "102") (name "unconnected-(U6A-CTRL_OUT0-PadD4)") (class "Default")
      (node (ref "U6") (pin "D4") (pinfunction "CTRL_OUT0_D4") (pintype "output"))
    )
    (net (code "103") (name "unconnected-(U6A-DNC-PadA3)") (class "Default")
      (node (ref "U6") (pin "A3") (pinfunction "DNC_A3") (pintype "passive+no_connect"))
    )
    (net (code "104") (name "unconnected-(U6A-VDDA1P3_RX_LO-PadE2)") (class "Default")
      (node (ref "U6") (pin "E2") (pinfunction "VDDA1P3_RX_LO_E2") (pintype "power_in"))
    )
    (net (code "105") (name "unconnected-(U6B-CLK_OUT-PadJ6)") (class "Default")
      (node (ref "U6") (pin "J6") (pinfunction "CLK_OUT_J6") (pintype "output"))
    )
    (net (code "106") (name "unconnected-(U6B-DATA_CLK_N-PadH11)") (class "Default")
      (node (ref "U6") (pin "H11") (pinfunction "DATA_CLK_N_H11") (pintype "output"))
    )
    (net (code "107") (name "unconnected-(U6B-DATA_CLK_P-PadG11)") (class "Default")
      (node (ref "U6") (pin "G11") (pinfunction "DATA_CLK_P_G11") (pintype "output"))
    )
    (net (code "108") (name "unconnected-(U6B-DNC-PadM3)") (class "Default")
      (node (ref "U6") (pin "M3") (pinfunction "DNC_M3") (pintype "passive"))
    )
    (net (code "109") (name "unconnected-(U6B-DNC-PadM11)") (class "Default")
      (node (ref "U6") (pin "M11") (pinfunction "DNC_M11") (pintype "passive"))
    )
    (net (code "110") (name "unconnected-(U6B-RX_FRAME_N-PadG7)") (class "Default")
      (node (ref "U6") (pin "G7") (pinfunction "RX_FRAME_N_G7") (pintype "output"))
    )
    (net (code "111") (name "unconnected-(U6B-RX_FRAME_P-PadG8)") (class "Default")
      (node (ref "U6") (pin "G8") (pinfunction "RX_FRAME_P_G8") (pintype "output"))
    )
    (net (code "112") (name "unconnected-(U6B-RX_VCO_LDO_OUT-PadG2)") (class "Default")
      (node (ref "U6") (pin "G2") (pinfunction "RX_VCO_LDO_OUT_G2") (pintype "power_in"))
    )
    (net (code "113") (name "unconnected-(U6B-VDDA1P1_RX_VCO-PadG3)") (class "Default")
      (node (ref "U6") (pin "G3") (pinfunction "VDDA1P1_RX_VCO_G3") (pintype "power_in"))
    )
    (net (code "114") (name "unconnected-(U6B-VDDA1P3_BB-PadK4)") (class "Default")
      (node (ref "U6") (pin "K4") (pinfunction "VDDA1P3_BB_K4") (pintype "power_in"))
    )
    (net (code "115") (name "unconnected-(U6B-VDDA1P3_RX_SYNTH-PadJ3)") (class "Default")
      (node (ref "U6") (pin "J3") (pinfunction "VDDA1P3_RX_SYNTH_J3") (pintype "power_in"))
    )
    (net (code "116") (name "unconnected-(U6B-VDDA1P3_TX_SYNTH-PadK3)") (class "Default")
      (node (ref "U6") (pin "K3") (pinfunction "VDDA1P3_TX_SYNTH_K3") (pintype "power_in"))
    )
    (net (code "117") (name "unconnected-(U6B-XTALN-PadM12)") (class "Default")
      (node (ref "U6") (pin "M12") (pinfunction "XTALN_M12") (pintype "input"))
    )
  )
)
